# nodeBoard.net
KiCad netlist of a schematic drawn in EAGLE
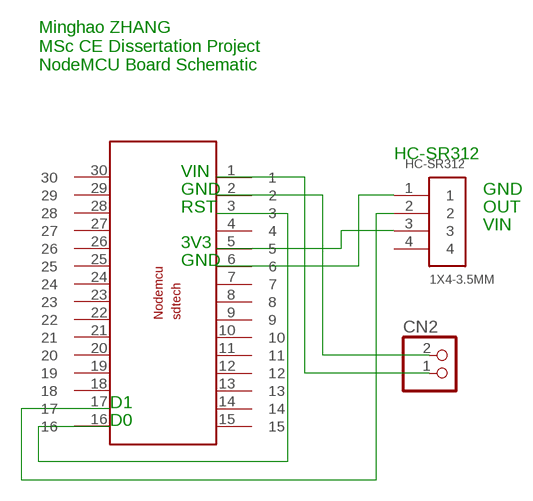
[diagram p0: schematic, sheet 1]

(export (version "E")
  (design (tool "Eeschema 10.0.6"))
  (components
    (comp (ref "CN2")
      (value "JST_2PIN-SMT")
      (footprint "eagle-import:JST-PH-2-SMT")
      (libsource (lib "eagle-import") (part "JST_2PIN-SMT"))
    )
    (comp (ref "HC-SR312")
      (value "1X4-3.5MM")
      (footprint "eagle-import:1X04-3.5MM")
      (libsource (lib "eagle-import") (part "1X4-3.5MM"))
    )
    (comp (ref "U$1")
      (value "NODEMCUESP8266")
      (footprint "eagle-import:NODEMCUESP8266")
      (libsource (lib "eagle-import") (part "NODEMCUESP8266"))
    )
  )
  (nets
    (net (code "1") (name "Net-(CN2-1)") (class "Default")
      (node (ref "CN2") (pin "2") (pinfunction "1_2") (pintype "passive"))
      (node (ref "U$1") (pin "2") (pinfunction "2_2") (pintype "bidirectional"))
    )
    (net (code "2") (name "Net-(CN2-2)") (class "Default")
      (node (ref "CN2") (pin "1") (pinfunction "2_1") (pintype "passive"))
      (node (ref "U$1") (pin "1") (pinfunction "1_1") (pintype "bidirectional"))
    )
    (net (code "3") (name "Net-(HC-SR312-Pad1)") (class "Default")
      (node (ref "HC-SR312") (pin "1") (pinfunction "1_1") (pintype "bidirectional"))
      (node (ref "U$1") (pin "6") (pinfunction "6_6") (pintype "bidirectional"))
    )
    (net (code "4") (name "Net-(HC-SR312-Pad2)") (class "Default")
      (node (ref "HC-SR312") (pin "2") (pinfunction "2_2") (pintype "bidirectional"))
      (node (ref "U$1") (pin "17") (pinfunction "17_17") (pintype "bidirectional"))
    )
    (net (code "5") (name "Net-(HC-SR312-Pad3)") (class "Default")
      (node (ref "HC-SR312") (pin "3") (pinfunction "3_3") (pintype "bidirectional"))
      (node (ref "U$1") (pin "5") (pinfunction "5_5") (pintype "bidirectional"))
    )
    (net (code "6") (name "Net-(U$1-Pad16)") (class "Default")
      (node (ref "U$1") (pin "16") (pinfunction "16_16") (pintype "bidirectional"))
      (node (ref "U$1") (pin "3") (pinfunction "3_3") (pintype "bidirectional"))
    )
    (net (code "7") (name "unconnected-(HC-SR312-Pad4)") (class "Default")
      (node (ref "HC-SR312") (pin "4") (pinfunction "4_4") (pintype "bidirectional"))
    )
    (net (code "8") (name "unconnected-(U$1-Pad4)") (class "Default")
      (node (ref "U$1") (pin "4") (pinfunction "4_4") (pintype "bidirectional"))
    )
    (net (code "9") (name "unconnected-(U$1-Pad7)") (class "Default")
      (node (ref "U$1") (pin "7") (pinfunction "7_7") (pintype "bidirectional"))
    )
    (net (code "10") (name "unconnected-(U$1-Pad8)") (class "Default")
      (node (ref "U$1") (pin "8") (pinfunction "8_8") (pintype "bidirectional"))
    )
    (net (code "11") (name "unconnected-(U$1-Pad9)") (class "Default")
      (node (ref "U$1") (pin "9") (pinfunction "9_9") (pintype "bidirectional"))
    )
    (net (code "12") (name "unconnected-(U$1-Pad10)") (class "Default")
      (node (ref "U$1") (pin "10") (pinfunction "10_10") (pintype "bidirectional"))
    )
    (net (code "13") (name "unconnected-(U$1-Pad11)") (class "Default")
      (node (ref "U$1") (pin "11") (pinfunction "11_11") (pintype "bidirectional"))
    )
    (net (code "14") (name "unconnected-(U$1-Pad12)") (class "Default")
      (node (ref "U$1") (pin "12") (pinfunction "12_12") (pintype "bidirectional"))
    )
    (net (code "15") (name "unconnected-(U$1-Pad13)") (class "Default")
      (node (ref "U$1") (pin "13") (pinfunction "13_13") (pintype "bidirectional"))
    )
    (net (code "16") (name "unconnected-(U$1-Pad14)") (class "Default")
      (node (ref "U$1") (pin "14") (pinfunction "14_14") (pintype "bidirectional"))
    )
    (net (code "17") (name "unconnected-(U$1-Pad15)") (class "Default")
      (node (ref "U$1") (pin "15") (pinfunction "15_15") (pintype "bidirectional"))
    )
    (net (code "18") (name "unconnected-(U$1-Pad18)") (class "Default")
      (node (ref "U$1") (pin "18") (pinfunction "18_18") (pintype "bidirectional"))
    )
    (net (code "19") (name "unconnected-(U$1-Pad19)") (class "Default")
      (node (ref "U$1") (pin "19") (pinfunction "19_19") (pintype "bidirectional"))
    )
    (net (code "20") (name "unconnected-(U$1-Pad20)") (class "Default")
      (node (ref "U$1") (pin "20") (pinfunction "20_20") (pintype "bidirectional"))
    )
    (net (code "21") (name "unconnected-(U$1-Pad21)") (class "Default")
      (node (ref "U$1") (pin "21") (pinfunction "21_21") (pintype "bidirectional"))
    )
    (net (code "22") (name "unconnected-(U$1-Pad22)") (class "Default")
      (node (ref "U$1") (pin "22") (pinfunction "22_22") (pintype "bidirectional"))
    )
    (net (code "23") (name "unconnected-(U$1-Pad23)") (class "Default")
      (node (ref "U$1") (pin "23") (pinfunction "23_23") (pintype "bidirectional"))
    )
    (net (code "24") (name "unconnected-(U$1-Pad24)") (class "Default")
      (node (ref "U$1") (pin "24") (pinfunction "24_24") (pintype "bidirectional"))
    )
    (net (code "25") (name "unconnected-(U$1-Pad25)") (class "Default")
      (node (ref "U$1") (pin "25") (pinfunction "25_25") (pintype "bidirectional"))
    )
    (net (code "26") (name "unconnected-(U$1-Pad26)") (class "Default")
      (node (ref "U$1") (pin "26") (pinfunction "26_26") (pintype "bidirectional"))
    )
    (net (code "27") (name "unconnected-(U$1-Pad27)") (class "Default")
      (node (ref "U$1") (pin "27") (pinfunction "27_27") (pintype "bidirectional"))
    )
    (net (code "28") (name "unconnected-(U$1-Pad28)") (class "Default")
      (node (ref "U$1") (pin "28") (pinfunction "28_28") (pintype "bidirectional"))
    )
    (net (code "29") (name "unconnected-(U$1-Pad29)") (class "Default")
      (node (ref "U$1") (pin "29") (pinfunction "29_29") (pintype "bidirectional"))
    )
    (net (code "30") (name "unconnected-(U$1-Pad30)") (class "Default")
      (node (ref "U$1") (pin "30") (pinfunction "30_30") (pintype "bidirectional"))
    )
  )
)
